# Quadcopter.net
KiCad netlist of a schematic drawn in EAGLE
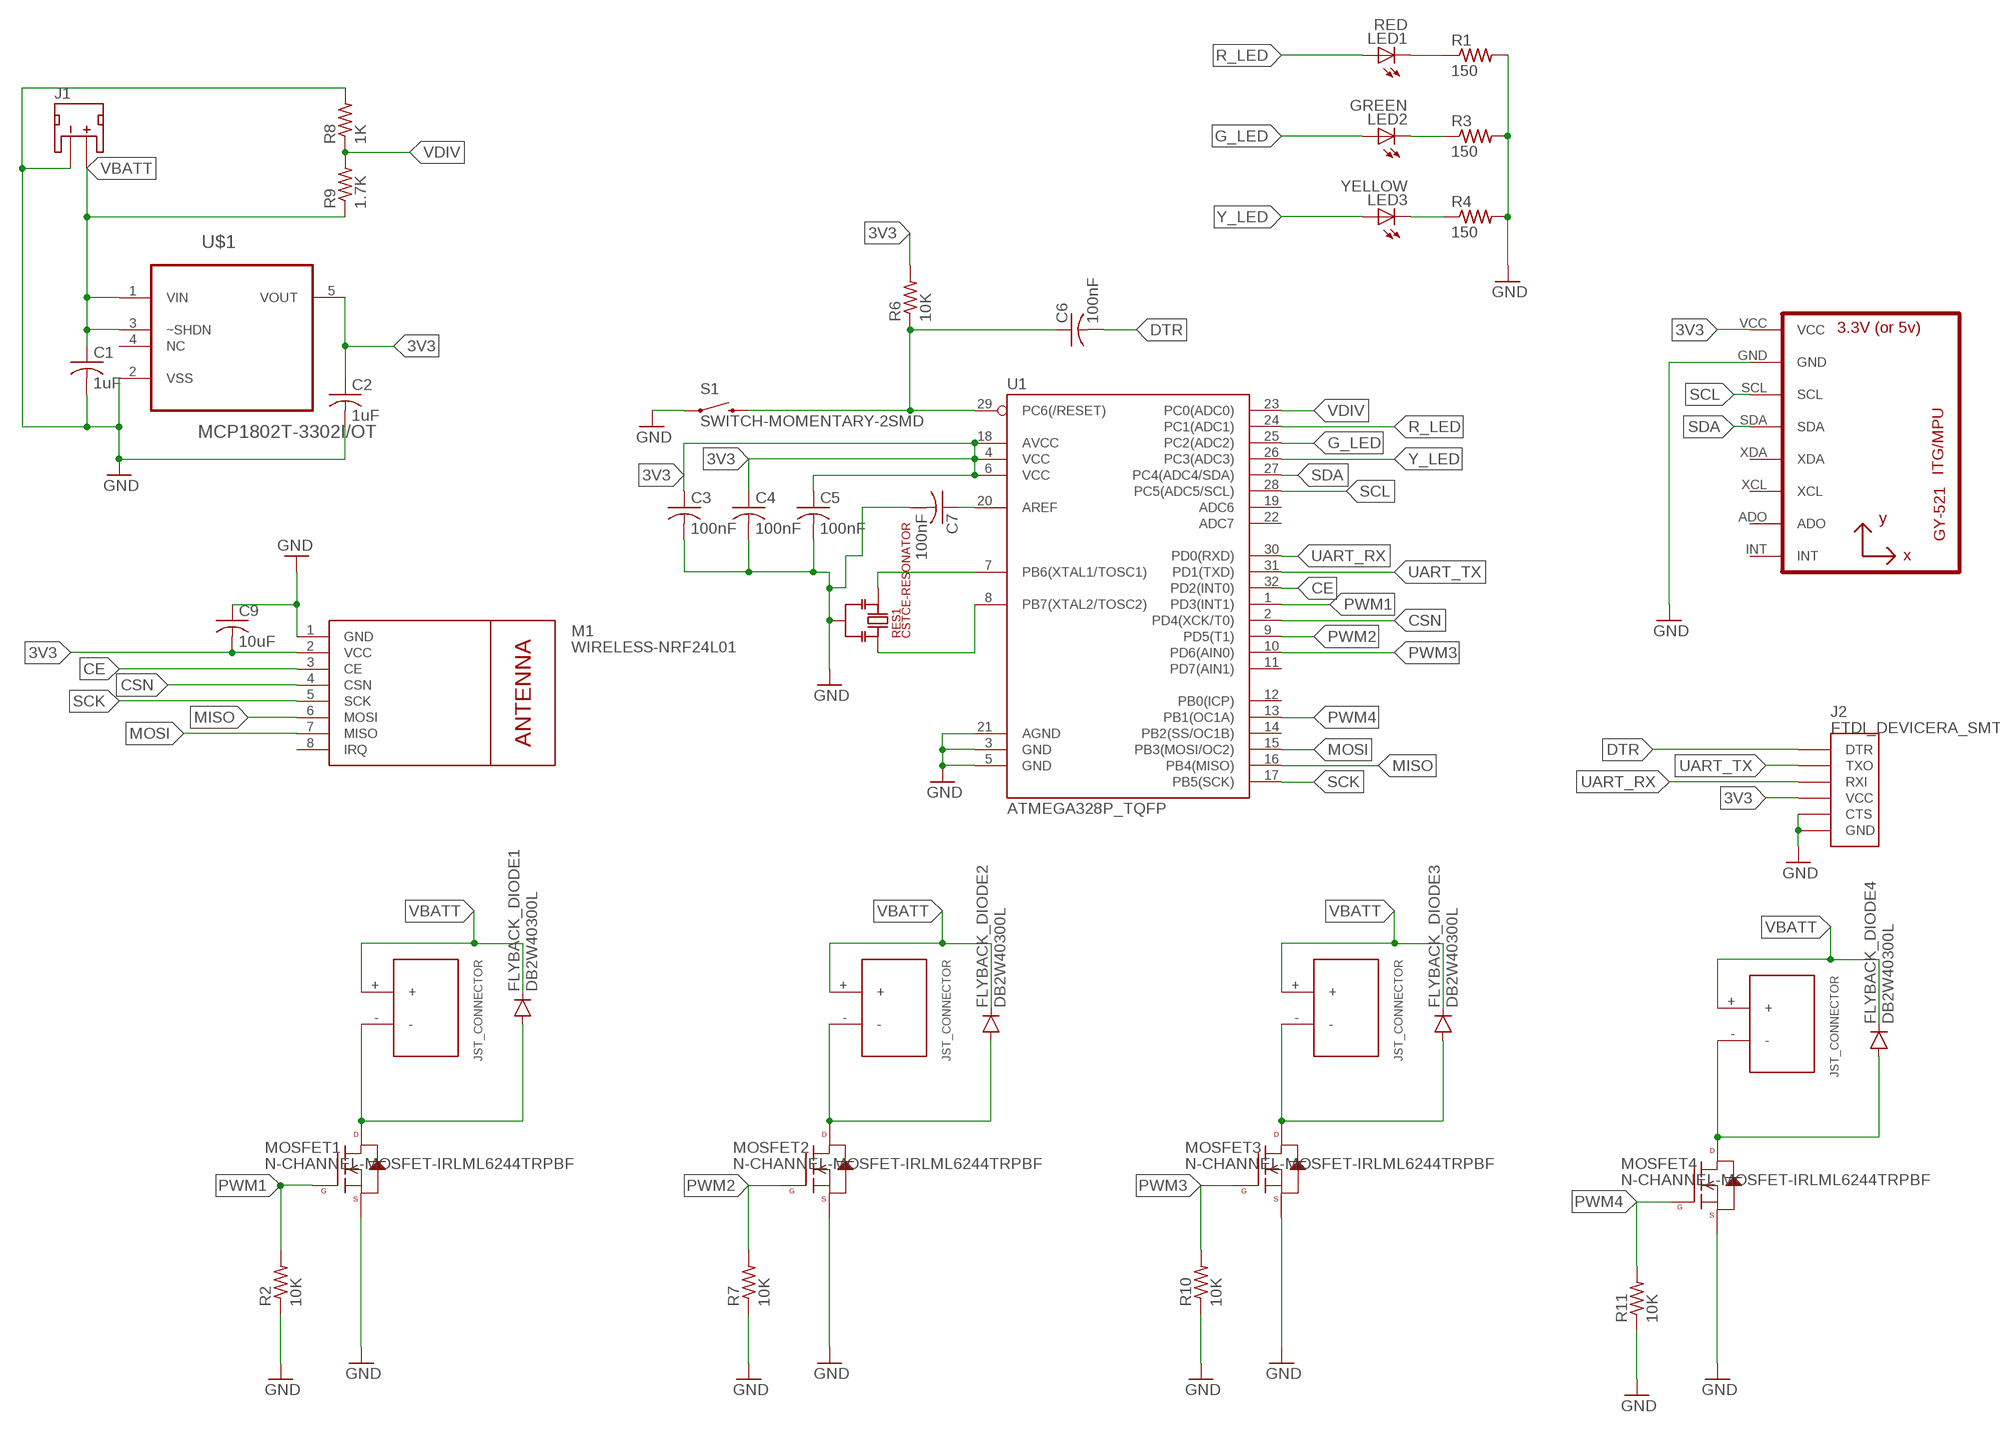
[diagram p0: schematic, sheet 1]

(export (version "E")
  (design (tool "Eeschema 10.0.6"))
  (components
    (comp (ref "C1")
      (value "1uF")
      (footprint "eagle-import:C0603")
      (libsource (lib "eagle-import") (part "C-USC0603"))
    )
    (comp (ref "C2")
      (value "1uF")
      (footprint "eagle-import:C0603")
      (libsource (lib "eagle-import") (part "C-USC0603"))
    )
    (comp (ref "C3")
      (value "100nF")
      (footprint "eagle-import:C0603")
      (libsource (lib "eagle-import") (part "C-USC0603"))
    )
    (comp (ref "C4")
      (value "100nF")
      (footprint "eagle-import:C0603")
      (libsource (lib "eagle-import") (part "C-USC0603"))
    )
    (comp (ref "C5")
      (value "100nF")
      (footprint "eagle-import:C0603")
      (libsource (lib "eagle-import") (part "C-USC0603"))
    )
    (comp (ref "C6")
      (value "100nF")
      (footprint "eagle-import:C0603")
      (libsource (lib "eagle-import") (part "C-USC0603"))
    )
    (comp (ref "C7")
      (value "100nF")
      (footprint "eagle-import:C0603")
      (libsource (lib "eagle-import") (part "C-USC0603"))
    )
    (comp (ref "C9")
      (value "10uF")
      (footprint "eagle-import:C0603")
      (libsource (lib "eagle-import") (part "C-USC0603"))
    )
    (comp (ref "FLYBACK_DIODE1")
      (value "DB2W40300L")
      (footprint "eagle-import:MINI2-F3-B")
      (libsource (lib "eagle-import") (part "DB2W40300L"))
    )
    (comp (ref "FLYBACK_DIODE2")
      (value "DB2W40300L")
      (footprint "eagle-import:MINI2-F3-B")
      (libsource (lib "eagle-import") (part "DB2W40300L"))
    )
    (comp (ref "FLYBACK_DIODE3")
      (value "DB2W40300L")
      (footprint "eagle-import:MINI2-F3-B")
      (libsource (lib "eagle-import") (part "DB2W40300L"))
    )
    (comp (ref "FLYBACK_DIODE4")
      (value "DB2W40300L")
      (footprint "eagle-import:MINI2-F3-B")
      (libsource (lib "eagle-import") (part "DB2W40300L"))
    )
    (comp (ref "J1")
      (value "JST_2MM_MALE")
      (footprint "eagle-import:JST-2-SMD")
      (libsource (lib "eagle-import") (part "JST_2MM_MALE"))
    )
    (comp (ref "J2")
      (value "FTDI_DEVICERA_SMT")
      (footprint "eagle-import:FTDI_DEVICE_RA_SMT")
      (libsource (lib "eagle-import") (part "FTDI_DEVICERA_SMT"))
    )
    (comp (ref "LED1")
      (value "RED")
      (footprint "eagle-import:CHIP-LED0603")
      (libsource (lib "eagle-import") (part "LEDCHIP-LED0603"))
    )
    (comp (ref "LED2")
      (value "GREEN")
      (footprint "eagle-import:CHIP-LED0603")
      (libsource (lib "eagle-import") (part "LEDCHIP-LED0603"))
    )
    (comp (ref "LED3")
      (value "YELLOW")
      (footprint "eagle-import:CHIP-LED0603")
      (libsource (lib "eagle-import") (part "LEDCHIP-LED0603"))
    )
    (comp (ref "M1")
      (value "WIRELESS-NRF24L01")
      (footprint "eagle-import:WIRELESS-NRF24L01")
      (libsource (lib "eagle-import") (part "WIRELESS-NRF24L01"))
    )
    (comp (ref "MOSFET1")
      (value "N-CHANNEL-MOSFET-IRLML6244TRPBF")
      (footprint "eagle-import:SOT23-3")
      (libsource (lib "eagle-import") (part "N-CHANNEL-MOSFET-IRLML6244TRPBF"))
    )
    (comp (ref "MOSFET2")
      (value "N-CHANNEL-MOSFET-IRLML6244TRPBF")
      (footprint "eagle-import:SOT23-3")
      (libsource (lib "eagle-import") (part "N-CHANNEL-MOSFET-IRLML6244TRPBF"))
    )
    (comp (ref "MOSFET3")
      (value "N-CHANNEL-MOSFET-IRLML6244TRPBF")
      (footprint "eagle-import:SOT23-3")
      (libsource (lib "eagle-import") (part "N-CHANNEL-MOSFET-IRLML6244TRPBF"))
    )
    (comp (ref "MOSFET4")
      (value "N-CHANNEL-MOSFET-IRLML6244TRPBF")
      (footprint "eagle-import:SOT23-3")
      (libsource (lib "eagle-import") (part "N-CHANNEL-MOSFET-IRLML6244TRPBF"))
    )
    (comp (ref "MOTOR")
      (value "JST_CONNECTOR_FEMALE")
      (footprint "eagle-import:JST_CONNECTOR_FEMALE")
      (libsource (lib "eagle-import") (part "JST_CONNECTOR_FEMALE"))
    )
    (comp (ref "MOTOR1")
      (value "JST_CONNECTOR_FEMALE")
      (footprint "eagle-import:JST_CONNECTOR_FEMALE")
      (libsource (lib "eagle-import") (part "JST_CONNECTOR_FEMALE"))
    )
    (comp (ref "MOTOR2")
      (value "JST_CONNECTOR_FEMALE")
      (footprint "eagle-import:JST_CONNECTOR_FEMALE")
      (libsource (lib "eagle-import") (part "JST_CONNECTOR_FEMALE"))
    )
    (comp (ref "MOTOR3")
      (value "JST_CONNECTOR_FEMALE")
      (footprint "eagle-import:JST_CONNECTOR_FEMALE")
      (libsource (lib "eagle-import") (part "JST_CONNECTOR_FEMALE"))
    )
    (comp (ref "R1")
      (value "150")
      (footprint "eagle-import:R0603")
      (libsource (lib "eagle-import") (part "R-US_R0603"))
    )
    (comp (ref "R2")
      (value "10K")
      (footprint "eagle-import:R0603")
      (libsource (lib "eagle-import") (part "R-US_R0603"))
    )
    (comp (ref "R3")
      (value "150")
      (footprint "eagle-import:R0603")
      (libsource (lib "eagle-import") (part "R-US_R0603"))
    )
    (comp (ref "R4")
      (value "150")
      (footprint "eagle-import:R0603")
      (libsource (lib "eagle-import") (part "R-US_R0603"))
    )
    (comp (ref "R6")
      (value "10K")
      (footprint "eagle-import:R0603")
      (libsource (lib "eagle-import") (part "R-US_R0603"))
    )
    (comp (ref "R7")
      (value "10K")
      (footprint "eagle-import:R0603")
      (libsource (lib "eagle-import") (part "R-US_R0603"))
    )
    (comp (ref "R8")
      (value "1K")
      (footprint "eagle-import:R0603")
      (libsource (lib "eagle-import") (part "R-US_R0603"))
    )
    (comp (ref "R9")
      (value "1.7K")
      (footprint "eagle-import:R0603")
      (libsource (lib "eagle-import") (part "R-US_R0603"))
    )
    (comp (ref "R10")
      (value "10K")
      (footprint "eagle-import:R0603")
      (libsource (lib "eagle-import") (part "R-US_R0603"))
    )
    (comp (ref "R11")
      (value "10K")
      (footprint "eagle-import:R0603")
      (libsource (lib "eagle-import") (part "R-US_R0603"))
    )
    (comp (ref "RES1")
      (value "CSTCE-RESONATOR")
      (footprint "eagle-import:CSTCE16M0V53-R0")
      (libsource (lib "eagle-import") (part "CSTCE-RESONATOR"))
    )
    (comp (ref "S1")
      (value "SWITCH-MOMENTARY-2SMD")
      (footprint "eagle-import:TACTILE-SWITCH-SMD")
      (libsource (lib "eagle-import") (part "SWITCH-MOMENTARY-2SMD"))
    )
    (comp (ref "U$1")
      (value "MCP1802T-3302I/OT")
      (footprint "eagle-import:SOT95P270X145-5N")
      (fields (field (name "MPN") "MCP1802T-3002I/OT"))
      (libsource (lib "eagle-import") (part "MCP1802T-3002I/OT"))
    )
    (comp (ref "U1")
      (value "ATMEGA328P_TQFP")
      (footprint "eagle-import:TQFP32-08")
      (libsource (lib "eagle-import") (part "ATMEGA328P_TQFP"))
    )
    (comp (ref "U3")
      (value "GY-521MPU6050")
      (footprint "eagle-import:GY-521")
      (libsource (lib "eagle-import") (part "GY-521MPU6050"))
    )
  )
  (nets
    (net (code "1") (name "3V3") (class "Default")
      (node (ref "C2") (pin "1") (pinfunction "1_1") (pintype "passive"))
      (node (ref "C3") (pin "1") (pinfunction "1_1") (pintype "passive"))
      (node (ref "C4") (pin "1") (pinfunction "1_1") (pintype "passive"))
      (node (ref "C5") (pin "1") (pinfunction "1_1") (pintype "passive"))
      (node (ref "C9") (pin "2") (pinfunction "2_2") (pintype "passive"))
      (node (ref "J2") (pin "4") (pinfunction "VCC_4") (pintype "bidirectional"))
      (node (ref "M1") (pin "2") (pinfunction "VCC_2") (pintype "power_in"))
      (node (ref "R6") (pin "2") (pinfunction "2_2") (pintype "passive"))
      (node (ref "U$1") (pin "5") (pinfunction "VOUT_5") (pintype "output"))
      (node (ref "U1") (pin "18") (pinfunction "AVCC_18") (pintype "bidirectional"))
      (node (ref "U1") (pin "4") (pinfunction "VCC_4") (pintype "bidirectional"))
      (node (ref "U1") (pin "6") (pinfunction "VCC_6") (pintype "bidirectional"))
      (node (ref "U3") (pin "VCC") (pinfunction "VCC_VCC") (pintype "bidirectional"))
    )
    (net (code "2") (name "CE") (class "Default")
      (node (ref "M1") (pin "3") (pinfunction "CE_3") (pintype "bidirectional"))
      (node (ref "U1") (pin "32") (pinfunction "PD2(INT0)_32") (pintype "bidirectional"))
    )
    (net (code "3") (name "CSN") (class "Default")
      (node (ref "M1") (pin "4") (pinfunction "CSN_4") (pintype "bidirectional"))
      (node (ref "U1") (pin "2") (pinfunction "PD4(XCK/T0)_2") (pintype "bidirectional"))
    )
    (net (code "4") (name "DTR") (class "Default")
      (node (ref "C6") (pin "2") (pinfunction "2_2") (pintype "passive"))
      (node (ref "J2") (pin "1") (pinfunction "DTR_1") (pintype "bidirectional"))
    )
    (net (code "5") (name "GND") (class "Default")
      (node (ref "C1") (pin "2") (pinfunction "2_2") (pintype "passive"))
      (node (ref "C2") (pin "2") (pinfunction "2_2") (pintype "passive"))
      (node (ref "C3") (pin "2") (pinfunction "2_2") (pintype "passive"))
      (node (ref "C4") (pin "2") (pinfunction "2_2") (pintype "passive"))
      (node (ref "C5") (pin "2") (pinfunction "2_2") (pintype "passive"))
      (node (ref "C7") (pin "2") (pinfunction "2_2") (pintype "passive"))
      (node (ref "C9") (pin "1") (pinfunction "1_1") (pintype "passive"))
      (node (ref "J1") (pin "1") (pinfunction "-_1") (pintype "bidirectional"))
      (node (ref "J2") (pin "5") (pinfunction "CTS_5") (pintype "bidirectional"))
      (node (ref "J2") (pin "6") (pinfunction "GND_6") (pintype "bidirectional"))
      (node (ref "M1") (pin "1") (pinfunction "GND_1") (pintype "power_in"))
      (node (ref "MOSFET1") (pin "2") (pinfunction "S_2") (pintype "passive"))
      (node (ref "MOSFET2") (pin "2") (pinfunction "S_2") (pintype "passive"))
      (node (ref "MOSFET3") (pin "2") (pinfunction "S_2") (pintype "passive"))
      (node (ref "MOSFET4") (pin "2") (pinfunction "S_2") (pintype "passive"))
      (node (ref "R1") (pin "2") (pinfunction "2_2") (pintype "passive"))
      (node (ref "R10") (pin "1") (pinfunction "1_1") (pintype "passive"))
      (node (ref "R11") (pin "1") (pinfunction "1_1") (pintype "passive"))
      (node (ref "R2") (pin "1") (pinfunction "1_1") (pintype "passive"))
      (node (ref "R3") (pin "2") (pinfunction "2_2") (pintype "passive"))
      (node (ref "R4") (pin "2") (pinfunction "2_2") (pintype "passive"))
      (node (ref "R7") (pin "1") (pinfunction "1_1") (pintype "passive"))
      (node (ref "R8") (pin "2") (pinfunction "2_2") (pintype "passive"))
      (node (ref "RES1") (pin "P$2") (pinfunction "P$2_P$2") (pintype "bidirectional"))
      (node (ref "S1") (pin "1") (pinfunction "1_1") (pintype "passive"))
      (node (ref "U$1") (pin "2") (pinfunction "VSS_2") (pintype "passive"))
      (node (ref "U1") (pin "21") (pinfunction "AGND_21") (pintype "bidirectional"))
      (node (ref "U1") (pin "3") (pinfunction "GND_3") (pintype "bidirectional"))
      (node (ref "U1") (pin "5") (pinfunction "GND_5") (pintype "bidirectional"))
      (node (ref "U3") (pin "GND") (pinfunction "GND_GND") (pintype "bidirectional"))
    )
    (net (code "6") (name "G_LED") (class "Default")
      (node (ref "LED2") (pin "A") (pinfunction "A_A") (pintype "passive"))
      (node (ref "U1") (pin "25") (pinfunction "PC2(ADC2)_25") (pintype "bidirectional"))
    )
    (net (code "7") (name "MISO") (class "Default")
      (node (ref "M1") (pin "6") (pinfunction "MOSI_6") (pintype "bidirectional"))
      (node (ref "U1") (pin "16") (pinfunction "PB4(MISO)_16") (pintype "bidirectional"))
    )
    (net (code "8") (name "MOSI") (class "Default")
      (node (ref "M1") (pin "7") (pinfunction "MISO_7") (pintype "bidirectional"))
      (node (ref "U1") (pin "15") (pinfunction "PB3(MOSI/OC2)_15") (pintype "bidirectional"))
    )
    (net (code "9") (name "Net-(FLYBACK_DIODE1-PPIN)") (class "Default")
      (node (ref "FLYBACK_DIODE1") (pin "POS") (pinfunction "PPIN_POS") (pintype "passive"))
      (node (ref "MOSFET1") (pin "3") (pinfunction "D_3") (pintype "passive"))
      (node (ref "MOTOR") (pin "-") (pinfunction "-_-") (pintype "bidirectional"))
    )
    (net (code "10") (name "Net-(FLYBACK_DIODE2-PPIN)") (class "Default")
      (node (ref "FLYBACK_DIODE2") (pin "POS") (pinfunction "PPIN_POS") (pintype "passive"))
      (node (ref "MOSFET2") (pin "3") (pinfunction "D_3") (pintype "passive"))
      (node (ref "MOTOR1") (pin "-") (pinfunction "-_-") (pintype "bidirectional"))
    )
    (net (code "11") (name "Net-(FLYBACK_DIODE3-PPIN)") (class "Default")
      (node (ref "FLYBACK_DIODE3") (pin "POS") (pinfunction "PPIN_POS") (pintype "passive"))
      (node (ref "MOSFET3") (pin "3") (pinfunction "D_3") (pintype "passive"))
      (node (ref "MOTOR2") (pin "-") (pinfunction "-_-") (pintype "bidirectional"))
    )
    (net (code "12") (name "Net-(FLYBACK_DIODE4-PPIN)") (class "Default")
      (node (ref "FLYBACK_DIODE4") (pin "POS") (pinfunction "PPIN_POS") (pintype "passive"))
      (node (ref "MOSFET4") (pin "3") (pinfunction "D_3") (pintype "passive"))
      (node (ref "MOTOR3") (pin "-") (pinfunction "-_-") (pintype "bidirectional"))
    )
    (net (code "13") (name "Net-(LED1-PadC)") (class "Default")
      (node (ref "LED1") (pin "C") (pinfunction "C_C") (pintype "passive"))
      (node (ref "R1") (pin "1") (pinfunction "1_1") (pintype "passive"))
    )
    (net (code "14") (name "Net-(LED2-PadC)") (class "Default")
      (node (ref "LED2") (pin "C") (pinfunction "C_C") (pintype "passive"))
      (node (ref "R3") (pin "1") (pinfunction "1_1") (pintype "passive"))
    )
    (net (code "15") (name "Net-(LED3-PadC)") (class "Default")
      (node (ref "LED3") (pin "C") (pinfunction "C_C") (pintype "passive"))
      (node (ref "R4") (pin "1") (pinfunction "1_1") (pintype "passive"))
    )
    (net (code "16") (name "Net-(S1-2)") (class "Default")
      (node (ref "C6") (pin "1") (pinfunction "1_1") (pintype "passive"))
      (node (ref "R6") (pin "1") (pinfunction "1_1") (pintype "passive"))
      (node (ref "S1") (pin "3") (pinfunction "2_3") (pintype "passive"))
      (node (ref "U1") (pin "29") (pinfunction "PC6(/RESET)_29") (pintype "bidirectional"))
    )
    (net (code "17") (name "Net-(U1-AREF)") (class "Default")
      (node (ref "C7") (pin "1") (pinfunction "1_1") (pintype "passive"))
      (node (ref "U1") (pin "20") (pinfunction "AREF_20") (pintype "bidirectional"))
    )
    (net (code "18") (name "Net-(U1-PB6(XTAL1{slash}TOSC1))") (class "Default")
      (node (ref "RES1") (pin "P$3") (pinfunction "P$3_P$3") (pintype "bidirectional"))
      (node (ref "U1") (pin "7") (pinfunction "PB6(XTAL1/TOSC1)_7") (pintype "bidirectional"))
    )
    (net (code "19") (name "Net-(U1-PB7(XTAL2{slash}TOSC2))") (class "Default")
      (node (ref "RES1") (pin "P$1") (pinfunction "P$1_P$1") (pintype "bidirectional"))
      (node (ref "U1") (pin "8") (pinfunction "PB7(XTAL2/TOSC2)_8") (pintype "bidirectional"))
    )
    (net (code "20") (name "PWM1") (class "Default")
      (node (ref "MOSFET1") (pin "1") (pinfunction "G_1") (pintype "passive"))
      (node (ref "R2") (pin "2") (pinfunction "2_2") (pintype "passive"))
      (node (ref "U1") (pin "1") (pinfunction "PD3(INT1)_1") (pintype "bidirectional"))
    )
    (net (code "21") (name "PWM2") (class "Default")
      (node (ref "MOSFET2") (pin "1") (pinfunction "G_1") (pintype "passive"))
      (node (ref "R7") (pin "2") (pinfunction "2_2") (pintype "passive"))
      (node (ref "U1") (pin "9") (pinfunction "PD5(T1)_9") (pintype "bidirectional"))
    )
    (net (code "22") (name "PWM3") (class "Default")
      (node (ref "MOSFET3") (pin "1") (pinfunction "G_1") (pintype "passive"))
      (node (ref "R10") (pin "2") (pinfunction "2_2") (pintype "passive"))
      (node (ref "U1") (pin "10") (pinfunction "PD6(AIN0)_10") (pintype "bidirectional"))
    )
    (net (code "23") (name "PWM4") (class "Default")
      (node (ref "MOSFET4") (pin "1") (pinfunction "G_1") (pintype "passive"))
      (node (ref "R11") (pin "2") (pinfunction "2_2") (pintype "passive"))
      (node (ref "U1") (pin "13") (pinfunction "PB1(OC1A)_13") (pintype "bidirectional"))
    )
    (net (code "24") (name "R_LED") (class "Default")
      (node (ref "LED1") (pin "A") (pinfunction "A_A") (pintype "passive"))
      (node (ref "U1") (pin "24") (pinfunction "PC1(ADC1)_24") (pintype "bidirectional"))
    )
    (net (code "25") (name "SCK") (class "Default")
      (node (ref "M1") (pin "5") (pinfunction "SCK_5") (pintype "bidirectional"))
      (node (ref "U1") (pin "17") (pinfunction "PB5(SCK)_17") (pintype "bidirectional"))
    )
    (net (code "26") (name "SCL") (class "Default")
      (node (ref "U1") (pin "28") (pinfunction "PC5(ADC5/SCL)_28") (pintype "bidirectional"))
      (node (ref "U3") (pin "SCL") (pinfunction "SCL_SCL") (pintype "bidirectional"))
    )
    (net (code "27") (name "SDA") (class "Default")
      (node (ref "U1") (pin "27") (pinfunction "PC4(ADC4/SDA)_27") (pintype "bidirectional"))
      (node (ref "U3") (pin "SDA") (pinfunction "SDA_SDA") (pintype "bidirectional"))
    )
    (net (code "28") (name "UART_RX") (class "Default")
      (node (ref "J2") (pin "3") (pinfunction "RXI_3") (pintype "bidirectional"))
      (node (ref "U1") (pin "30") (pinfunction "PD0(RXD)_30") (pintype "bidirectional"))
    )
    (net (code "29") (name "UART_TX") (class "Default")
      (node (ref "J2") (pin "2") (pinfunction "TXO_2") (pintype "bidirectional"))
      (node (ref "U1") (pin "31") (pinfunction "PD1(TXD)_31") (pintype "bidirectional"))
    )
    (net (code "30") (name "VBATT") (class "Default")
      (node (ref "C1") (pin "1") (pinfunction "1_1") (pintype "passive"))
      (node (ref "FLYBACK_DIODE1") (pin "NEG") (pinfunction "GPIN_NEG") (pintype "passive"))
      (node (ref "FLYBACK_DIODE2") (pin "NEG") (pinfunction "GPIN_NEG") (pintype "passive"))
      (node (ref "FLYBACK_DIODE3") (pin "NEG") (pinfunction "GPIN_NEG") (pintype "passive"))
      (node (ref "FLYBACK_DIODE4") (pin "NEG") (pinfunction "GPIN_NEG") (pintype "passive"))
      (node (ref "J1") (pin "2") (pinfunction "+_2") (pintype "bidirectional"))
      (node (ref "MOTOR") (pin "+") (pinfunction "+_+") (pintype "bidirectional"))
      (node (ref "MOTOR1") (pin "+") (pinfunction "+_+") (pintype "bidirectional"))
      (node (ref "MOTOR2") (pin "+") (pinfunction "+_+") (pintype "bidirectional"))
      (node (ref "MOTOR3") (pin "+") (pinfunction "+_+") (pintype "bidirectional"))
      (node (ref "R9") (pin "1") (pinfunction "1_1") (pintype "passive"))
      (node (ref "U$1") (pin "1") (pinfunction "VIN_1") (pintype "power_in"))
      (node (ref "U$1") (pin "3") (pinfunction "~{SHDN}_3") (pintype "input"))
    )
    (net (code "31") (name "VDIV") (class "Default")
      (node (ref "R8") (pin "1") (pinfunction "1_1") (pintype "passive"))
      (node (ref "R9") (pin "2") (pinfunction "2_2") (pintype "passive"))
      (node (ref "U1") (pin "23") (pinfunction "PC0(ADC0)_23") (pintype "bidirectional"))
    )
    (net (code "32") (name "Y_LED") (class "Default")
      (node (ref "LED3") (pin "A") (pinfunction "A_A") (pintype "passive"))
      (node (ref "U1") (pin "26") (pinfunction "PC3(ADC3)_26") (pintype "bidirectional"))
    )
    (net (code "33") (name "unconnected-(J1-PAD1-PadNC1)") (class "Default")
      (node (ref "J1") (pin "NC1") (pinfunction "PAD1_NC1") (pintype "bidirectional"))
    )
    (net (code "34") (name "unconnected-(J1-PAD2-PadNC2)") (class "Default")
      (node (ref "J1") (pin "NC2") (pinfunction "PAD2_NC2") (pintype "bidirectional"))
    )
    (net (code "35") (name "unconnected-(M1-IRQ-Pad8)") (class "Default")
      (node (ref "M1") (pin "8") (pinfunction "IRQ_8") (pintype "bidirectional"))
    )
    (net (code "36") (name "unconnected-(U$1-NC-Pad4)") (class "Default")
      (node (ref "U$1") (pin "4") (pinfunction "NC_4") (pintype "no_connect"))
    )
    (net (code "37") (name "unconnected-(U1-ADC6-Pad19)") (class "Default")
      (node (ref "U1") (pin "19") (pinfunction "ADC6_19") (pintype "bidirectional"))
    )
    (net (code "38") (name "unconnected-(U1-ADC7-Pad22)") (class "Default")
      (node (ref "U1") (pin "22") (pinfunction "ADC7_22") (pintype "bidirectional"))
    )
    (net (code "39") (name "unconnected-(U1-PB0(ICP)-Pad12)") (class "Default")
      (node (ref "U1") (pin "12") (pinfunction "PB0(ICP)_12") (pintype "bidirectional"))
    )
    (net (code "40") (name "unconnected-(U1-PB2(SS{slash}OC1B)-Pad14)") (class "Default")
      (node (ref "U1") (pin "14") (pinfunction "PB2(SS/OC1B)_14") (pintype "bidirectional"))
    )
    (net (code "41") (name "unconnected-(U1-PD7(AIN1)-Pad11)") (class "Default")
      (node (ref "U1") (pin "11") (pinfunction "PD7(AIN1)_11") (pintype "bidirectional"))
    )
    (net (code "42") (name "unconnected-(U3-PadADO)") (class "Default")
      (node (ref "U3") (pin "ADO") (pinfunction "ADO_ADO") (pintype "bidirectional"))
    )
    (net (code "43") (name "unconnected-(U3-PadINT)") (class "Default")
      (node (ref "U3") (pin "INT") (pinfunction "INT_INT") (pintype "bidirectional"))
    )
    (net (code "44") (name "unconnected-(U3-PadXCL)") (class "Default")
      (node (ref "U3") (pin "XCL") (pinfunction "XCL_XCL") (pintype "bidirectional"))
    )
    (net (code "45") (name "unconnected-(U3-PadXDA)") (class "Default")
      (node (ref "U3") (pin "XDA") (pinfunction "XDA_XDA") (pintype "bidirectional"))
    )
  )
)
